# Kitchen_Light_Driver_1_1.net
KiCad netlist of a schematic drawn in EAGLE
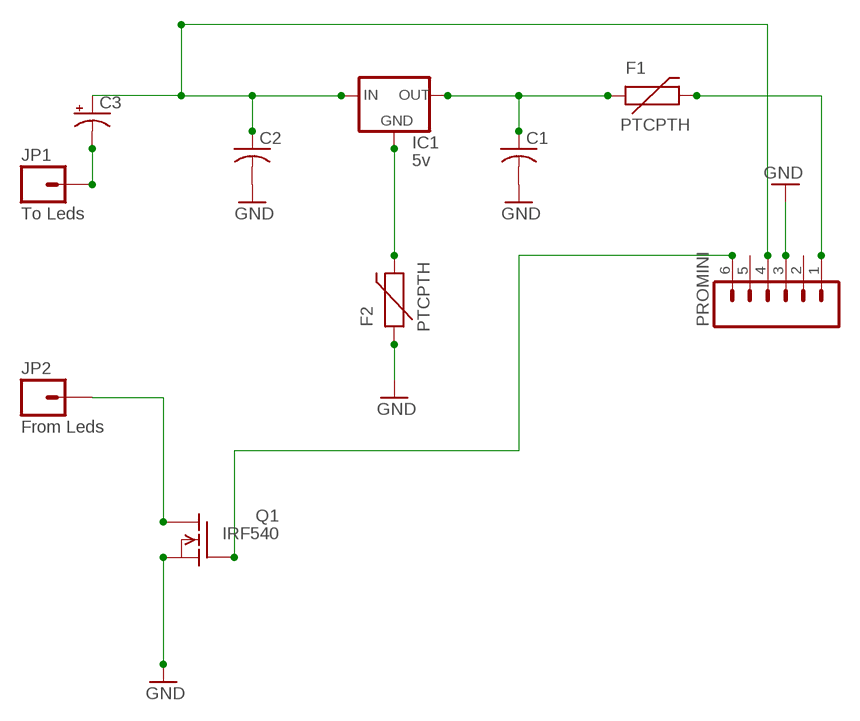
[diagram p0: schematic, sheet 1]

(export (version "E")
  (design (tool "Eeschema 10.0.6"))
  (components
    (comp (ref "C1")
      (value "C-US025-024X044")
      (footprint "eagle-import:C025-024X044")
      (libsource (lib "eagle-import") (part "C-US025-024X044"))
    )
    (comp (ref "C2")
      (value "C-US025-024X044")
      (footprint "eagle-import:C025-024X044")
      (libsource (lib "eagle-import") (part "C-US025-024X044"))
    )
    (comp (ref "C3")
      (value "CPOL-USE3.5-8")
      (footprint "eagle-import:E3,5-8")
      (libsource (lib "eagle-import") (part "CPOL-USE3.5-8"))
    )
    (comp (ref "F1")
      (value "PTCPTH")
      (footprint "eagle-import:PTC")
      (libsource (lib "eagle-import") (part "PTCPTH"))
    )
    (comp (ref "F2")
      (value "PTCPTH")
      (footprint "eagle-import:PTC")
      (libsource (lib "eagle-import") (part "PTCPTH"))
    )
    (comp (ref "IC1")
      (value "5v")
      (footprint "eagle-import:78XXL")
      (libsource (lib "eagle-import") (part "78XXL"))
    )
    (comp (ref "JP1")
      (value "To Leds")
      (footprint "eagle-import:1X01")
      (libsource (lib "eagle-import") (part "M01PTH"))
    )
    (comp (ref "JP2")
      (value "From Leds")
      (footprint "eagle-import:1X01")
      (libsource (lib "eagle-import") (part "M01PTH"))
    )
    (comp (ref "PROMINI")
      (value "M06SIP")
      (footprint "eagle-import:1X06")
      (libsource (lib "eagle-import") (part "M06SIP"))
    )
    (comp (ref "Q1")
      (value "IRF540")
      (footprint "eagle-import:TO220")
      (libsource (lib "eagle-import") (part "BUZ11"))
    )
  )
  (nets
    (net (code "1") (name "GND") (class "Default")
      (node (ref "C1") (pin "2") (pinfunction "2_2") (pintype "passive"))
      (node (ref "C2") (pin "2") (pinfunction "2_2") (pintype "passive"))
      (node (ref "F2") (pin "P$1") (pinfunction "1_P$1") (pintype "bidirectional"))
      (node (ref "PROMINI") (pin "3") (pinfunction "3_3") (pintype "passive"))
      (node (ref "Q1") (pin "3") (pinfunction "S_3") (pintype "passive"))
    )
    (net (code "2") (name "Net-(C2-Pad1)") (class "Default")
      (node (ref "C2") (pin "1") (pinfunction "1_1") (pintype "passive"))
      (node (ref "C3") (pin "+") (pinfunction "+_+") (pintype "passive"))
      (node (ref "IC1") (pin "IN") (pinfunction "IN_IN") (pintype "input"))
      (node (ref "PROMINI") (pin "4") (pinfunction "4_4") (pintype "passive"))
    )
    (net (code "3") (name "Net-(C3-Pad-)") (class "Default")
      (node (ref "C3") (pin "-") (pinfunction "-_-") (pintype "passive"))
      (node (ref "JP1") (pin "1") (pinfunction "1_1") (pintype "passive"))
    )
    (net (code "4") (name "Net-(F1-1)") (class "Default")
      (node (ref "C1") (pin "1") (pinfunction "1_1") (pintype "passive"))
      (node (ref "F1") (pin "P$1") (pinfunction "1_P$1") (pintype "bidirectional"))
      (node (ref "IC1") (pin "OUT") (pinfunction "OUT_OUT") (pintype "passive"))
    )
    (net (code "5") (name "Net-(F1-2)") (class "Default")
      (node (ref "F1") (pin "P$2") (pinfunction "2_P$2") (pintype "bidirectional"))
      (node (ref "PROMINI") (pin "1") (pinfunction "1_1") (pintype "passive"))
    )
    (net (code "6") (name "Net-(F2-2)") (class "Default")
      (node (ref "F2") (pin "P$2") (pinfunction "2_P$2") (pintype "bidirectional"))
      (node (ref "IC1") (pin "GND") (pinfunction "GND_GND") (pintype "input"))
    )
    (net (code "7") (name "Net-(Q1-D)") (class "Default")
      (node (ref "JP2") (pin "1") (pinfunction "1_1") (pintype "passive"))
      (node (ref "Q1") (pin "2") (pinfunction "D_2") (pintype "passive"))
    )
    (net (code "8") (name "Net-(Q1-G)") (class "Default")
      (node (ref "PROMINI") (pin "6") (pinfunction "6_6") (pintype "passive"))
      (node (ref "Q1") (pin "1") (pinfunction "G_1") (pintype "passive"))
    )
    (net (code "9") (name "unconnected-(PROMINI-Pad2)") (class "Default")
      (node (ref "PROMINI") (pin "2") (pinfunction "2_2") (pintype "passive"))
    )
    (net (code "10") (name "unconnected-(PROMINI-Pad5)") (class "Default")
      (node (ref "PROMINI") (pin "5") (pinfunction "5_5") (pintype "passive"))
    )
  )
)
